# Sheet2motorcontrol.net
KiCad netlist of a schematic drawn in Altium Designer
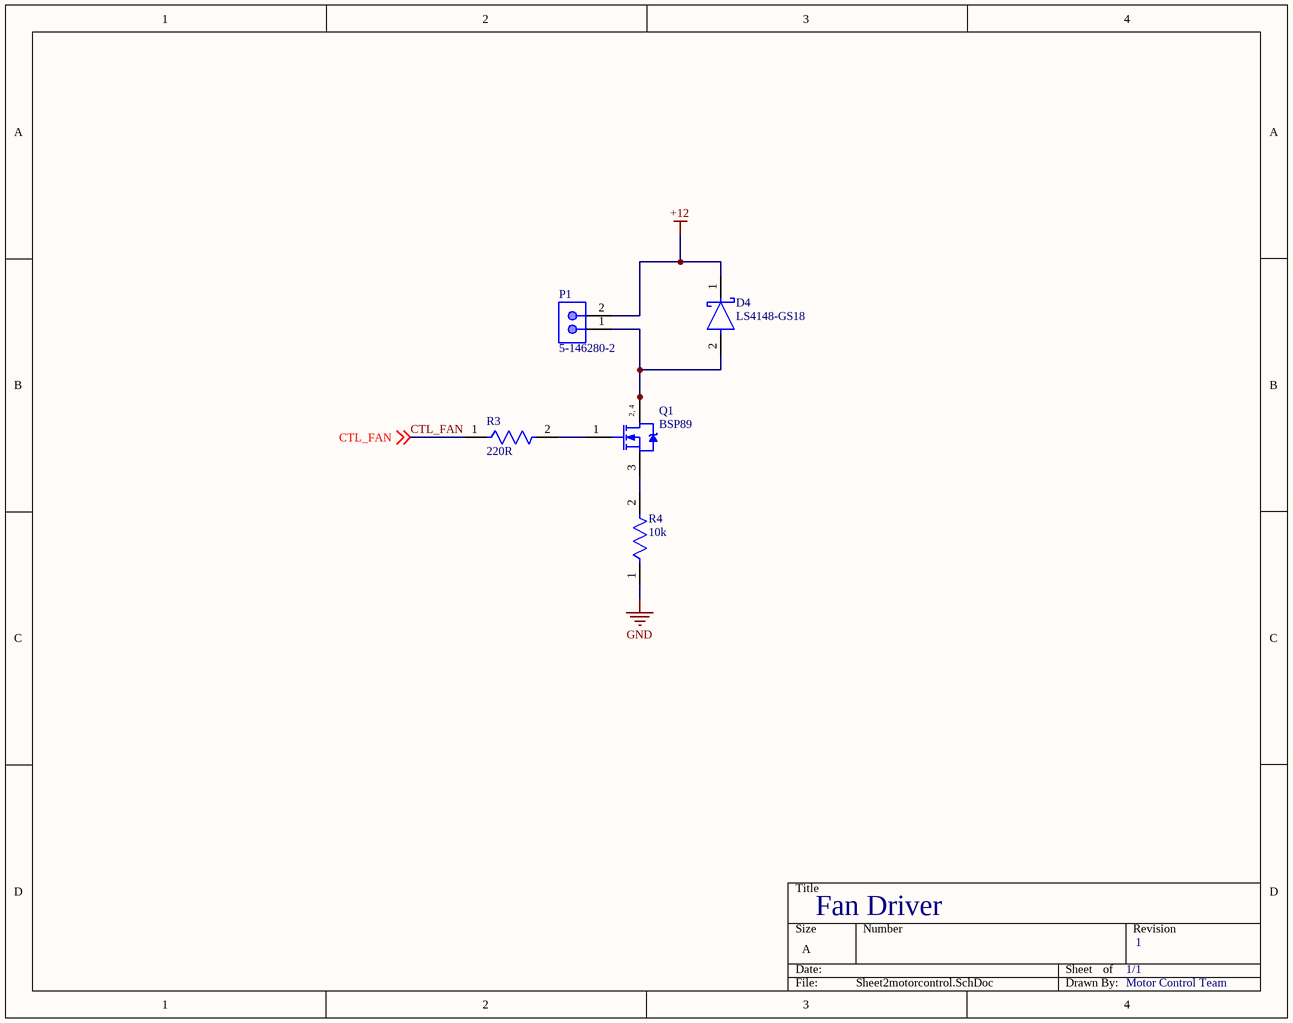
[diagram p0: Sheet2motorcontrol.SchDoc]

(export (version "E")
  (design (tool "Eeschema 10.0.6"))
  (components
    (comp (ref "D4")
      (value "LS4148-GS18")
      (footprint "FP-6_560-5006_01-4-MFG")
      (description "DIODE GEN PURP 75V 150MA SOD80")
      (fields
        (field (name "MANUFACTURER") "Vishay")
        (field (name "OCTOPART") "https://octopart.com/ls4148-gs18-vishay-55507867")
      )
      (libsource (lib "Altium Content Vault") (part "1d6ec82d83fb6aee721767c19dac4b9"))
    )
    (comp (ref "P1")
      (value "5-146280-2")
      (footprint "TECO-5-146280-2_V")
      (fields (field (name "MANUFACTURER") "TE Connectivity"))
      (libsource (lib "Altium Content Vault") (part "CN-1P-M-R2"))
    )
    (comp (ref "Q1")
      (value "BSP89")
      (footprint "INF-PG-SOT223_SC-73_M")
      (fields (field (name "MANUFACTURER") "Infineon"))
      (libsource (lib "Altium Content Vault") (part "INF-NEMOS-GDSD-4-B"))
    )
    (comp (ref "R3")
      (value "220R")
      (footprint "FP-CR1206-MFG")
      (description "Thick Film Chip Resistors 1206 330Ω 0.25W 1% 100ppm/°C")
      (fields (field (name "TOLERANCE") "1%"))
      (libsource (lib "Altium Content Vault") (part "1029c3af85768c4190bb7ad29bc67b5"))
    )
    (comp (ref "R4")
      (value "10k")
      (footprint "FP-CR1206-MFG")
      (description "Thick Film Chip Resistors 1206 330Ω 0.25W 1% 100ppm/°C")
      (fields (field (name "TOLERANCE") "1%"))
      (libsource (lib "Altium Content Vault") (part "1029c3af85768c4190bb7ad29bc67b5"))
    )
  )
  (nets
    (net (code "1") (name "+12") (class "Default")
      (node (ref "D4") (pin "1") (pinfunction "C_1") (pintype "passive"))
      (node (ref "P1") (pin "2") (pinfunction "2_2") (pintype "passive"))
    )
    (net (code "2") (name "CTL_FAN") (class "Default")
      (node (ref "R3") (pin "1") (pinfunction "1_1") (pintype "passive"))
    )
    (net (code "3") (name "GND") (class "Default")
      (node (ref "R4") (pin "1") (pinfunction "1_1") (pintype "passive"))
    )
    (net (code "4") (name "Net-(D4-A)") (class "Default")
      (node (ref "D4") (pin "2") (pinfunction "A_2") (pintype "passive"))
      (node (ref "P1") (pin "1") (pinfunction "1_1") (pintype "passive"))
      (node (ref "Q1") (pin "2") (pinfunction "DRAIN_2") (pintype "passive"))
      (node (ref "Q1") (pin "4") (pinfunction "DRAIN_4") (pintype "passive"))
    )
    (net (code "5") (name "Net-(Q1-GATE)") (class "Default")
      (node (ref "Q1") (pin "1") (pinfunction "GATE_1") (pintype "passive"))
      (node (ref "R3") (pin "2") (pinfunction "2_2") (pintype "passive"))
    )
    (net (code "6") (name "Net-(Q1-SOURCE)") (class "Default")
      (node (ref "Q1") (pin "3") (pinfunction "SOURCE_3") (pintype "passive"))
      (node (ref "R4") (pin "2") (pinfunction "2_2") (pintype "passive"))
    )
  )
)
